# Desoldering_Station.net
KiCad netlist of a schematic drawn in EAGLE
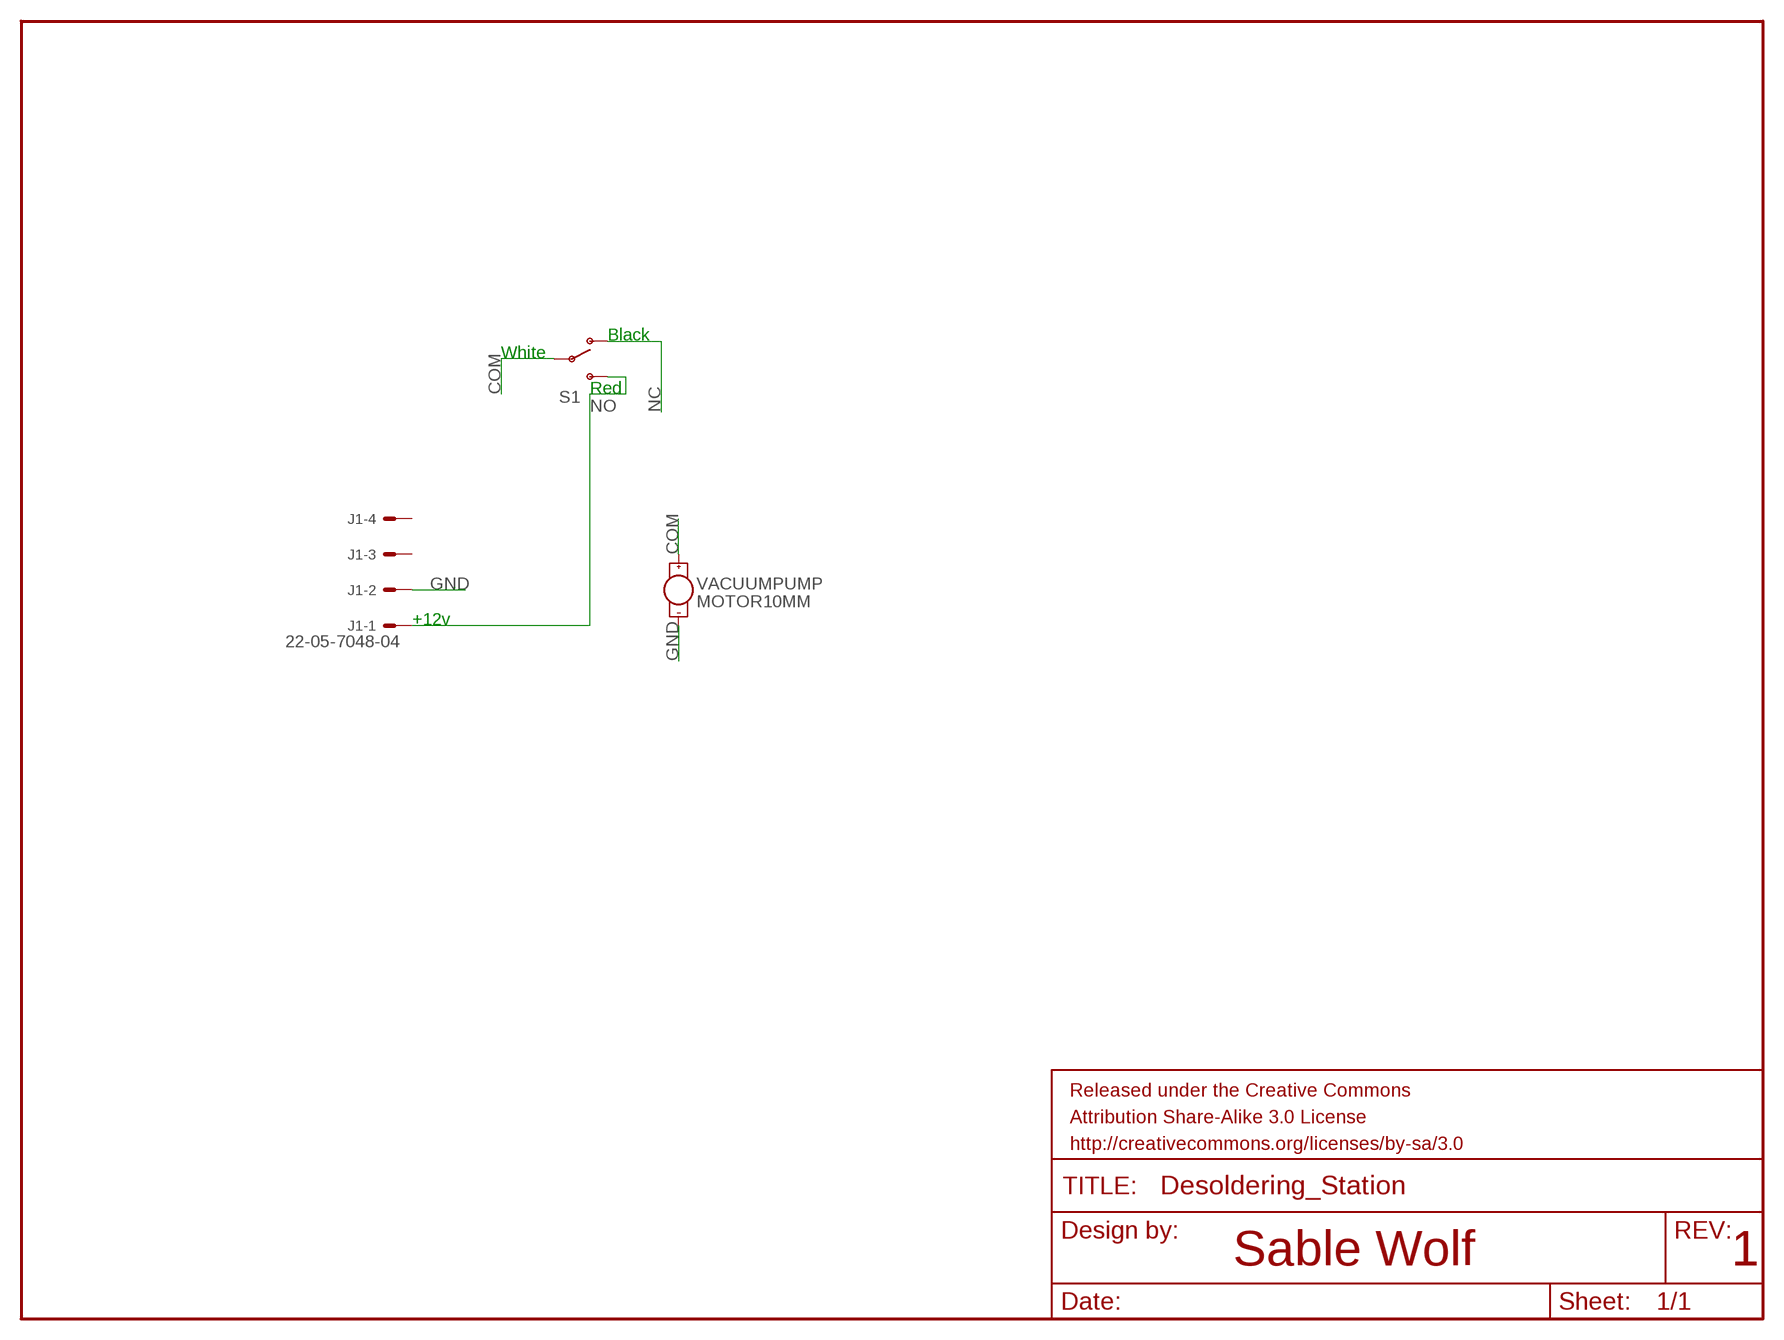
[diagram p0: schematic, sheet 1]

(export (version "E")
  (design (tool "Eeschema 10.0.6"))
  (components
    (comp (ref "FRAME1")
      (value "FRAME-LETTER")
      (footprint "eagle-import:CREATIVE_COMMONS")
      (libsource (lib "eagle-import") (part "FRAME-LETTER"))
    )
    (comp (ref "J1")
      (value "22-05-7048-04")
      (footprint "eagle-import:7395-04")
      (libsource (lib "eagle-import") (part "22-?-0405-7048"))
    )
    (comp (ref "S1")
      (value "SWITCH-SPDTKIT")
      (footprint "eagle-import:SWITCH-SPDT_KIT")
      (libsource (lib "eagle-import") (part "SWITCH-SPDTKIT"))
    )
    (comp (ref "VACUUMPUMP")
      (value "MOTOR10MM")
      (footprint "eagle-import:VIBE-MOTOR-10MM")
      (libsource (lib "eagle-import") (part "MOTOR10MM"))
    )
  )
  (nets
    (net (code "1") (name "/COM") (class "Default")
      (node (ref "S1") (pin "2") (pinfunction "P_2") (pintype "passive"))
      (node (ref "VACUUMPUMP") (pin "+") (pinfunction "+_+") (pintype "bidirectional"))
    )
    (net (code "2") (name "/GND") (class "Default")
      (node (ref "J1") (pin "2") (pinfunction "S_2") (pintype "passive"))
      (node (ref "VACUUMPUMP") (pin "-") (pinfunction "-_-") (pintype "bidirectional"))
    )
    (net (code "3") (name "/NC") (class "Default")
      (node (ref "S1") (pin "1") (pinfunction "O_1") (pintype "passive"))
    )
    (net (code "4") (name "/NO") (class "Default")
      (node (ref "J1") (pin "1") (pinfunction "S_1") (pintype "passive"))
      (node (ref "S1") (pin "3") (pinfunction "S_3") (pintype "passive"))
    )
    (net (code "5") (name "unconnected-(J1C-S-Pad3)") (class "Default")
      (node (ref "J1") (pin "3") (pinfunction "S_3") (pintype "passive"))
    )
    (net (code "6") (name "unconnected-(J1D-S-Pad4)") (class "Default")
      (node (ref "J1") (pin "4") (pinfunction "S_4") (pintype "passive"))
    )
  )
)
